# 2_waffling60-ALPS_matrix.net
KiCad netlist of a schematic drawn in Altium Designer
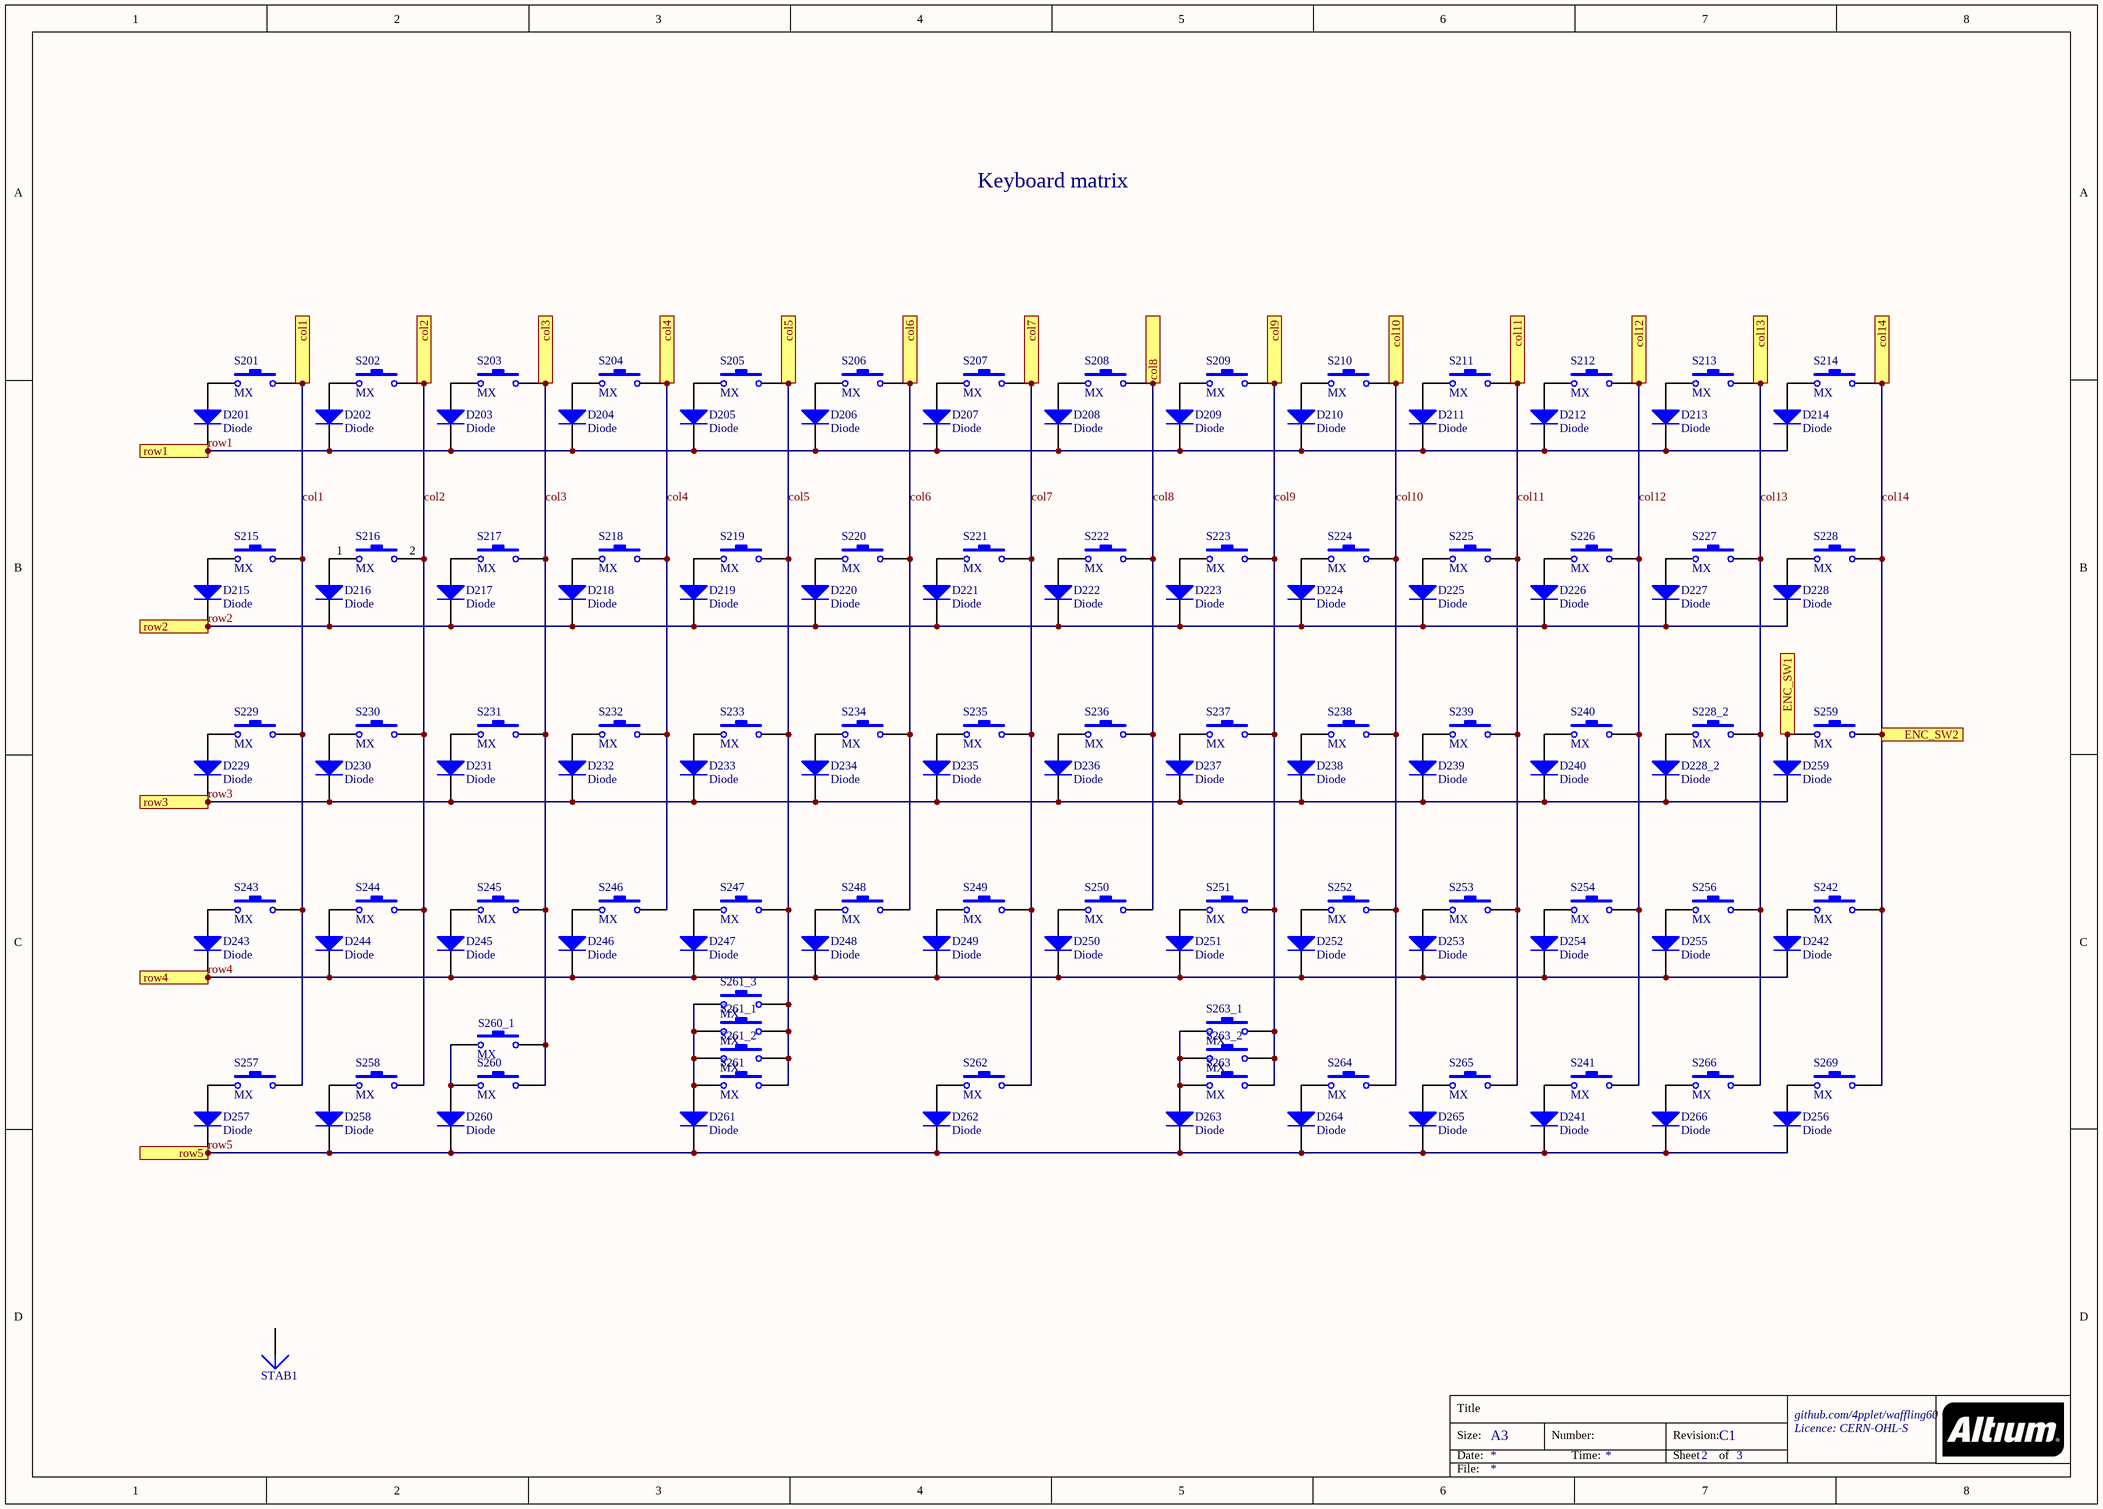
[diagram p0: 2_waffling60-ALPS_matrix.SchDoc]

(export (version "E")
  (design (tool "Eeschema 10.0.6"))
  (components
    (comp (ref "D201")
      (value "Diode")
      (footprint "SOD-123")
      (description "Default Diode")
      (fields (field (name "LCSC PART #") "C81598") (field (name "MRF.PART") "1N4148W"))
      (libsource (lib "Miscellaneous Devices") (part "Diode"))
    )
    (comp (ref "D202")
      (value "Diode")
      (footprint "SOD-123")
      (description "Default Diode")
      (fields (field (name "LCSC PART #") "C81598") (field (name "MRF.PART") "1N4148W"))
      (libsource (lib "Miscellaneous Devices") (part "Diode"))
    )
    (comp (ref "D203")
      (value "Diode")
      (footprint "SOD-123")
      (description "Default Diode")
      (fields (field (name "LCSC PART #") "C81598") (field (name "MRF.PART") "1N4148W"))
      (libsource (lib "Miscellaneous Devices") (part "Diode"))
    )
    (comp (ref "D204")
      (value "Diode")
      (footprint "SOD-123")
      (description "Default Diode")
      (fields (field (name "LCSC PART #") "C81598") (field (name "MRF.PART") "1N4148W"))
      (libsource (lib "Miscellaneous Devices") (part "Diode"))
    )
    (comp (ref "D205")
      (value "Diode")
      (footprint "SOD-123")
      (description "Default Diode")
      (fields (field (name "LCSC PART #") "C81598") (field (name "MRF.PART") "1N4148W"))
      (libsource (lib "Miscellaneous Devices") (part "Diode"))
    )
    (comp (ref "D206")
      (value "Diode")
      (footprint "SOD-123")
      (description "Default Diode")
      (fields (field (name "LCSC PART #") "C81598") (field (name "MRF.PART") "1N4148W"))
      (libsource (lib "Miscellaneous Devices") (part "Diode"))
    )
    (comp (ref "D207")
      (value "Diode")
      (footprint "SOD-123")
      (description "Default Diode")
      (fields (field (name "LCSC PART #") "C81598") (field (name "MRF.PART") "1N4148W"))
      (libsource (lib "Miscellaneous Devices") (part "Diode"))
    )
    (comp (ref "D208")
      (value "Diode")
      (footprint "SOD-123")
      (description "Default Diode")
      (fields (field (name "LCSC PART #") "C81598") (field (name "MRF.PART") "1N4148W"))
      (libsource (lib "Miscellaneous Devices") (part "Diode"))
    )
    (comp (ref "D209")
      (value "Diode")
      (footprint "SOD-123")
      (description "Default Diode")
      (fields (field (name "LCSC PART #") "C81598") (field (name "MRF.PART") "1N4148W"))
      (libsource (lib "Miscellaneous Devices") (part "Diode"))
    )
    (comp (ref "D210")
      (value "Diode")
      (footprint "SOD-123")
      (description "Default Diode")
      (fields (field (name "LCSC PART #") "C81598") (field (name "MRF.PART") "1N4148W"))
      (libsource (lib "Miscellaneous Devices") (part "Diode"))
    )
    (comp (ref "D211")
      (value "Diode")
      (footprint "SOD-123")
      (description "Default Diode")
      (fields (field (name "LCSC PART #") "C81598") (field (name "MRF.PART") "1N4148W"))
      (libsource (lib "Miscellaneous Devices") (part "Diode"))
    )
    (comp (ref "D212")
      (value "Diode")
      (footprint "SOD-123")
      (description "Default Diode")
      (fields (field (name "LCSC PART #") "C81598") (field (name "MRF.PART") "1N4148W"))
      (libsource (lib "Miscellaneous Devices") (part "Diode"))
    )
    (comp (ref "D213")
      (value "Diode")
      (footprint "SOD-123")
      (description "Default Diode")
      (fields (field (name "LCSC PART #") "C81598") (field (name "MRF.PART") "1N4148W"))
      (libsource (lib "Miscellaneous Devices") (part "Diode"))
    )
    (comp (ref "D214")
      (value "Diode")
      (footprint "SOD-123")
      (description "Default Diode")
      (fields (field (name "LCSC PART #") "C81598") (field (name "MRF.PART") "1N4148W"))
      (libsource (lib "Miscellaneous Devices") (part "Diode"))
    )
    (comp (ref "D215")
      (value "Diode")
      (footprint "SOD-123")
      (description "Default Diode")
      (fields (field (name "LCSC PART #") "C81598") (field (name "MRF.PART") "1N4148W"))
      (libsource (lib "Miscellaneous Devices") (part "Diode"))
    )
    (comp (ref "D216")
      (value "Diode")
      (footprint "SOD-123")
      (description "Default Diode")
      (fields (field (name "LCSC PART #") "C81598") (field (name "MRF.PART") "1N4148W"))
      (libsource (lib "Miscellaneous Devices") (part "Diode"))
    )
    (comp (ref "D217")
      (value "Diode")
      (footprint "SOD-123")
      (description "Default Diode")
      (fields (field (name "LCSC PART #") "C81598") (field (name "MRF.PART") "1N4148W"))
      (libsource (lib "Miscellaneous Devices") (part "Diode"))
    )
    (comp (ref "D218")
      (value "Diode")
      (footprint "SOD-123")
      (description "Default Diode")
      (fields (field (name "LCSC PART #") "C81598") (field (name "MRF.PART") "1N4148W"))
      (libsource (lib "Miscellaneous Devices") (part "Diode"))
    )
    (comp (ref "D219")
      (value "Diode")
      (footprint "SOD-123")
      (description "Default Diode")
      (fields (field (name "LCSC PART #") "C81598") (field (name "MRF.PART") "1N4148W"))
      (libsource (lib "Miscellaneous Devices") (part "Diode"))
    )
    (comp (ref "D220")
      (value "Diode")
      (footprint "SOD-123")
      (description "Default Diode")
      (fields (field (name "LCSC PART #") "C81598") (field (name "MRF.PART") "1N4148W"))
      (libsource (lib "Miscellaneous Devices") (part "Diode"))
    )
    (comp (ref "D221")
      (value "Diode")
      (footprint "SOD-123")
      (description "Default Diode")
      (fields (field (name "LCSC PART #") "C81598") (field (name "MRF.PART") "1N4148W"))
      (libsource (lib "Miscellaneous Devices") (part "Diode"))
    )
    (comp (ref "D222")
      (value "Diode")
      (footprint "SOD-123")
      (description "Default Diode")
      (fields (field (name "LCSC PART #") "C81598") (field (name "MRF.PART") "1N4148W"))
      (libsource (lib "Miscellaneous Devices") (part "Diode"))
    )
    (comp (ref "D223")
      (value "Diode")
      (footprint "SOD-123")
      (description "Default Diode")
      (fields (field (name "LCSC PART #") "C81598") (field (name "MRF.PART") "1N4148W"))
      (libsource (lib "Miscellaneous Devices") (part "Diode"))
    )
    (comp (ref "D224")
      (value "Diode")
      (footprint "SOD-123")
      (description "Default Diode")
      (fields (field (name "LCSC PART #") "C81598") (field (name "MRF.PART") "1N4148W"))
      (libsource (lib "Miscellaneous Devices") (part "Diode"))
    )
    (comp (ref "D225")
      (value "Diode")
      (footprint "SOD-123")
      (description "Default Diode")
      (fields (field (name "LCSC PART #") "C81598") (field (name "MRF.PART") "1N4148W"))
      (libsource (lib "Miscellaneous Devices") (part "Diode"))
    )
    (comp (ref "D226")
      (value "Diode")
      (footprint "SOD-123")
      (description "Default Diode")
      (fields (field (name "LCSC PART #") "C81598") (field (name "MRF.PART") "1N4148W"))
      (libsource (lib "Miscellaneous Devices") (part "Diode"))
    )
    (comp (ref "D227")
      (value "Diode")
      (footprint "SOD-123")
      (description "Default Diode")
      (fields (field (name "LCSC PART #") "C81598") (field (name "MRF.PART") "1N4148W"))
      (libsource (lib "Miscellaneous Devices") (part "Diode"))
    )
    (comp (ref "D228")
      (value "Diode")
      (footprint "SOD-123")
      (description "Default Diode")
      (fields (field (name "LCSC PART #") "C81598") (field (name "MRF.PART") "1N4148W"))
      (libsource (lib "Miscellaneous Devices") (part "Diode"))
    )
    (comp (ref "D228_2")
      (value "Diode")
      (footprint "SOD-123")
      (description "Default Diode")
      (fields (field (name "LCSC PART #") "C81598") (field (name "MRF.PART") "1N4148W"))
      (libsource (lib "Miscellaneous Devices") (part "Diode"))
    )
    (comp (ref "D229")
      (value "Diode")
      (footprint "SOD-123")
      (description "Default Diode")
      (fields (field (name "LCSC PART #") "C81598") (field (name "MRF.PART") "1N4148W"))
      (libsource (lib "Miscellaneous Devices") (part "Diode"))
    )
    (comp (ref "D230")
      (value "Diode")
      (footprint "SOD-123")
      (description "Default Diode")
      (fields (field (name "LCSC PART #") "C81598") (field (name "MRF.PART") "1N4148W"))
      (libsource (lib "Miscellaneous Devices") (part "Diode"))
    )
    (comp (ref "D231")
      (value "Diode")
      (footprint "SOD-123")
      (description "Default Diode")
      (fields (field (name "LCSC PART #") "C81598") (field (name "MRF.PART") "1N4148W"))
      (libsource (lib "Miscellaneous Devices") (part "Diode"))
    )
    (comp (ref "D232")
      (value "Diode")
      (footprint "SOD-123")
      (description "Default Diode")
      (fields (field (name "LCSC PART #") "C81598") (field (name "MRF.PART") "1N4148W"))
      (libsource (lib "Miscellaneous Devices") (part "Diode"))
    )
    (comp (ref "D233")
      (value "Diode")
      (footprint "SOD-123")
      (description "Default Diode")
      (fields (field (name "LCSC PART #") "C81598") (field (name "MRF.PART") "1N4148W"))
      (libsource (lib "Miscellaneous Devices") (part "Diode"))
    )
    (comp (ref "D234")
      (value "Diode")
      (footprint "SOD-123")
      (description "Default Diode")
      (fields (field (name "LCSC PART #") "C81598") (field (name "MRF.PART") "1N4148W"))
      (libsource (lib "Miscellaneous Devices") (part "Diode"))
    )
    (comp (ref "D235")
      (value "Diode")
      (footprint "SOD-123")
      (description "Default Diode")
      (fields (field (name "LCSC PART #") "C81598") (field (name "MRF.PART") "1N4148W"))
      (libsource (lib "Miscellaneous Devices") (part "Diode"))
    )
    (comp (ref "D236")
      (value "Diode")
      (footprint "SOD-123")
      (description "Default Diode")
      (fields (field (name "LCSC PART #") "C81598") (field (name "MRF.PART") "1N4148W"))
      (libsource (lib "Miscellaneous Devices") (part "Diode"))
    )
    (comp (ref "D237")
      (value "Diode")
      (footprint "SOD-123")
      (description "Default Diode")
      (fields (field (name "LCSC PART #") "C81598") (field (name "MRF.PART") "1N4148W"))
      (libsource (lib "Miscellaneous Devices") (part "Diode"))
    )
    (comp (ref "D238")
      (value "Diode")
      (footprint "SOD-123")
      (description "Default Diode")
      (fields (field (name "LCSC PART #") "C81598") (field (name "MRF.PART") "1N4148W"))
      (libsource (lib "Miscellaneous Devices") (part "Diode"))
    )
    (comp (ref "D239")
      (value "Diode")
      (footprint "SOD-123")
      (description "Default Diode")
      (fields (field (name "LCSC PART #") "C81598") (field (name "MRF.PART") "1N4148W"))
      (libsource (lib "Miscellaneous Devices") (part "Diode"))
    )
    (comp (ref "D240")
      (value "Diode")
      (footprint "SOD-123")
      (description "Default Diode")
      (fields (field (name "LCSC PART #") "C81598") (field (name "MRF.PART") "1N4148W"))
      (libsource (lib "Miscellaneous Devices") (part "Diode"))
    )
    (comp (ref "D241")
      (value "Diode")
      (footprint "SOD-123")
      (description "Default Diode")
      (fields (field (name "LCSC PART #") "C81598") (field (name "MRF.PART") "1N4148W"))
      (libsource (lib "Miscellaneous Devices") (part "Diode"))
    )
    (comp (ref "D242")
      (value "Diode")
      (footprint "SOD-123")
      (description "Default Diode")
      (fields (field (name "LCSC PART #") "C81598") (field (name "MRF.PART") "1N4148W"))
      (libsource (lib "Miscellaneous Devices") (part "Diode"))
    )
    (comp (ref "D243")
      (value "Diode")
      (footprint "SOD-123")
      (description "Default Diode")
      (fields (field (name "LCSC PART #") "C81598") (field (name "MRF.PART") "1N4148W"))
      (libsource (lib "Miscellaneous Devices") (part "Diode"))
    )
    (comp (ref "D244")
      (value "Diode")
      (footprint "SOD-123")
      (description "Default Diode")
      (fields (field (name "LCSC PART #") "C81598") (field (name "MRF.PART") "1N4148W"))
      (libsource (lib "Miscellaneous Devices") (part "Diode"))
    )
    (comp (ref "D245")
      (value "Diode")
      (footprint "SOD-123")
      (description "Default Diode")
      (fields (field (name "LCSC PART #") "C81598") (field (name "MRF.PART") "1N4148W"))
      (libsource (lib "Miscellaneous Devices") (part "Diode"))
    )
    (comp (ref "D246")
      (value "Diode")
      (footprint "SOD-123")
      (description "Default Diode")
      (fields (field (name "LCSC PART #") "C81598") (field (name "MRF.PART") "1N4148W"))
      (libsource (lib "Miscellaneous Devices") (part "Diode"))
    )
    (comp (ref "D247")
      (value "Diode")
      (footprint "SOD-123")
      (description "Default Diode")
      (fields (field (name "LCSC PART #") "C81598") (field (name "MRF.PART") "1N4148W"))
      (libsource (lib "Miscellaneous Devices") (part "Diode"))
    )
    (comp (ref "D248")
      (value "Diode")
      (footprint "SOD-123")
      (description "Default Diode")
      (fields (field (name "LCSC PART #") "C81598") (field (name "MRF.PART") "1N4148W"))
      (libsource (lib "Miscellaneous Devices") (part "Diode"))
    )
    (comp (ref "D249")
      (value "Diode")
      (footprint "SOD-123")
      (description "Default Diode")
      (fields (field (name "LCSC PART #") "C81598") (field (name "MRF.PART") "1N4148W"))
      (libsource (lib "Miscellaneous Devices") (part "Diode"))
    )
    (comp (ref "D250")
      (value "Diode")
      (footprint "SOD-123")
      (description "Default Diode")
      (fields (field (name "LCSC PART #") "C81598") (field (name "MRF.PART") "1N4148W"))
      (libsource (lib "Miscellaneous Devices") (part "Diode"))
    )
    (comp (ref "D251")
      (value "Diode")
      (footprint "SOD-123")
      (description "Default Diode")
      (fields (field (name "LCSC PART #") "C81598") (field (name "MRF.PART") "1N4148W"))
      (libsource (lib "Miscellaneous Devices") (part "Diode"))
    )
    (comp (ref "D252")
      (value "Diode")
      (footprint "SOD-123")
      (description "Default Diode")
      (fields (field (name "LCSC PART #") "C81598") (field (name "MRF.PART") "1N4148W"))
      (libsource (lib "Miscellaneous Devices") (part "Diode"))
    )
    (comp (ref "D253")
      (value "Diode")
      (footprint "SOD-123")
      (description "Default Diode")
      (fields (field (name "LCSC PART #") "C81598") (field (name "MRF.PART") "1N4148W"))
      (libsource (lib "Miscellaneous Devices") (part "Diode"))
    )
    (comp (ref "D254")
      (value "Diode")
      (footprint "SOD-123")
      (description "Default Diode")
      (fields (field (name "LCSC PART #") "C81598") (field (name "MRF.PART") "1N4148W"))
      (libsource (lib "Miscellaneous Devices") (part "Diode"))
    )
    (comp (ref "D255")
      (value "Diode")
      (footprint "SOD-123")
      (description "Default Diode")
      (fields (field (name "LCSC PART #") "C81598") (field (name "MRF.PART") "1N4148W"))
      (libsource (lib "Miscellaneous Devices") (part "Diode"))
    )
    (comp (ref "D256")
      (value "Diode")
      (footprint "SOD-123")
      (description "Default Diode")
      (fields (field (name "LCSC PART #") "C81598") (field (name "MRF.PART") "1N4148W"))
      (libsource (lib "Miscellaneous Devices") (part "Diode"))
    )
    (comp (ref "D257")
      (value "Diode")
      (footprint "SOD-123")
      (description "Default Diode")
      (fields (field (name "LCSC PART #") "C81598") (field (name "MRF.PART") "1N4148W"))
      (libsource (lib "Miscellaneous Devices") (part "Diode"))
    )
    (comp (ref "D258")
      (value "Diode")
      (footprint "SOD-123")
      (description "Default Diode")
      (fields (field (name "LCSC PART #") "C81598") (field (name "MRF.PART") "1N4148W"))
      (libsource (lib "Miscellaneous Devices") (part "Diode"))
    )
    (comp (ref "D259")
      (value "Diode")
      (footprint "SOD-123")
      (description "Default Diode")
      (fields (field (name "LCSC PART #") "C81598") (field (name "MRF.PART") "1N4148W"))
      (libsource (lib "Miscellaneous Devices") (part "Diode"))
    )
    (comp (ref "D260")
      (value "Diode")
      (footprint "SOD-123")
      (description "Default Diode")
      (fields (field (name "LCSC PART #") "C81598") (field (name "MRF.PART") "1N4148W"))
      (libsource (lib "Miscellaneous Devices") (part "Diode"))
    )
    (comp (ref "D261")
      (value "Diode")
      (footprint "SOD-123")
      (description "Default Diode")
      (fields (field (name "LCSC PART #") "C81598") (field (name "MRF.PART") "1N4148W"))
      (libsource (lib "Miscellaneous Devices") (part "Diode"))
    )
    (comp (ref "D262")
      (value "Diode")
      (footprint "SOD-123")
      (description "Default Diode")
      (fields (field (name "LCSC PART #") "C81598") (field (name "MRF.PART") "1N4148W"))
      (libsource (lib "Miscellaneous Devices") (part "Diode"))
    )
    (comp (ref "D263")
      (value "Diode")
      (footprint "SOD-123")
      (description "Default Diode")
      (fields (field (name "LCSC PART #") "C81598") (field (name "MRF.PART") "1N4148W"))
      (libsource (lib "Miscellaneous Devices") (part "Diode"))
    )
    (comp (ref "D264")
      (value "Diode")
      (footprint "SOD-123")
      (description "Default Diode")
      (fields (field (name "LCSC PART #") "C81598") (field (name "MRF.PART") "1N4148W"))
      (libsource (lib "Miscellaneous Devices") (part "Diode"))
    )
    (comp (ref "D265")
      (value "Diode")
      (footprint "SOD-123")
      (description "Default Diode")
      (fields (field (name "LCSC PART #") "C81598") (field (name "MRF.PART") "1N4148W"))
      (libsource (lib "Miscellaneous Devices") (part "Diode"))
    )
    (comp (ref "D266")
      (value "Diode")
      (footprint "SOD-123")
      (description "Default Diode")
      (fields (field (name "LCSC PART #") "C81598") (field (name "MRF.PART") "1N4148W"))
      (libsource (lib "Miscellaneous Devices") (part "Diode"))
    )
    (comp (ref "S201")
      (value "MX")
      (footprint "Alps-switch - switched pol")
      (description "Switch")
      (libsource (lib "Miscellaneous Devices") (part "SW-PB"))
    )
    (comp (ref "S202")
      (value "MX")
      (footprint "Alps-switch - switched pol")
      (description "Switch")
      (libsource (lib "Miscellaneous Devices") (part "SW-PB"))
    )
    (comp (ref "S203")
      (value "MX")
      (footprint "Alps-switch - switched pol")
      (description "Switch")
      (libsource (lib "Miscellaneous Devices") (part "SW-PB"))
    )
    (comp (ref "S204")
      (value "MX")
      (footprint "Alps-switch - switched pol")
      (description "Switch")
      (libsource (lib "Miscellaneous Devices") (part "SW-PB"))
    )
    (comp (ref "S205")
      (value "MX")
      (footprint "Alps-switch - switched pol")
      (description "Switch")
      (libsource (lib "Miscellaneous Devices") (part "SW-PB"))
    )
    (comp (ref "S206")
      (value "MX")
      (footprint "Alps-switch - switched pol")
      (description "Switch")
      (libsource (lib "Miscellaneous Devices") (part "SW-PB"))
    )
    (comp (ref "S207")
      (value "MX")
      (footprint "Alps-switch - switched pol")
      (description "Switch")
      (libsource (lib "Miscellaneous Devices") (part "SW-PB"))
    )
    (comp (ref "S208")
      (value "MX")
      (footprint "Alps-switch - switched pol")
      (description "Switch")
      (libsource (lib "Miscellaneous Devices") (part "SW-PB"))
    )
    (comp (ref "S209")
      (value "MX")
      (footprint "Alps-switch - switched pol")
      (description "Switch")
      (libsource (lib "Miscellaneous Devices") (part "SW-PB"))
    )
    (comp (ref "S210")
      (value "MX")
      (footprint "Alps-switch - switched pol")
      (description "Switch")
      (libsource (lib "Miscellaneous Devices") (part "SW-PB"))
    )
    (comp (ref "S211")
      (value "MX")
      (footprint "Alps-switch - switched pol")
      (description "Switch")
      (libsource (lib "Miscellaneous Devices") (part "SW-PB"))
    )
    (comp (ref "S212")
      (value "MX")
      (footprint "Alps-switch - switched pol")
      (description "Switch")
      (libsource (lib "Miscellaneous Devices") (part "SW-PB"))
    )
    (comp (ref "S213")
      (value "MX")
      (footprint "Alps-switch - switched pol")
      (description "Switch")
      (libsource (lib "Miscellaneous Devices") (part "SW-PB"))
    )
    (comp (ref "S214")
      (value "MX")
      (footprint "Alps-switch")
      (description "Switch")
      (libsource (lib "Miscellaneous Devices") (part "SW-PB"))
    )
    (comp (ref "S215")
      (value "MX")
      (footprint "Alps-switch - switched pol")
      (description "TAB")
      (libsource (lib "Miscellaneous Devices") (part "SW-PB"))
    )
    (comp (ref "S216")
      (value "MX")
      (footprint "Alps-switch")
      (description "Switch")
      (libsource (lib "") (part "SW-PB_1"))
    )
    (comp (ref "S217")
      (value "MX")
      (footprint "Alps-switch - switched pol")
      (description "Switch")
      (libsource (lib "Miscellaneous Devices") (part "SW-PB"))
    )
    (comp (ref "S218")
      (value "MX")
      (footprint "Alps-switch - switched pol")
      (description "Switch")
      (libsource (lib "Miscellaneous Devices") (part "SW-PB"))
    )
    (comp (ref "S219")
      (value "MX")
      (footprint "Alps-switch - switched pol")
      (description "Switch")
      (libsource (lib "Miscellaneous Devices") (part "SW-PB"))
    )
    (comp (ref "S220")
      (value "MX")
      (footprint "Alps-switch - switched pol")
      (description "Switch")
      (libsource (lib "Miscellaneous Devices") (part "SW-PB"))
    )
    (comp (ref "S221")
      (value "MX")
      (footprint "Alps-switch - switched pol")
      (description "Switch")
      (libsource (lib "Miscellaneous Devices") (part "SW-PB"))
    )
    (comp (ref "S222")
      (value "MX")
      (footprint "Alps-switch - switched pol")
      (description "Switch")
      (libsource (lib "Miscellaneous Devices") (part "SW-PB"))
    )
    (comp (ref "S223")
      (value "MX")
      (footprint "Alps-switch - switched pol")
      (description "Switch")
      (libsource (lib "Miscellaneous Devices") (part "SW-PB"))
    )
    (comp (ref "S224")
      (value "MX")
      (footprint "Alps-switch - switched pol")
      (description "Switch")
      (libsource (lib "Miscellaneous Devices") (part "SW-PB"))
    )
    (comp (ref "S225")
      (value "MX")
      (footprint "Alps-switch - switched pol")
      (description "Switch")
      (libsource (lib "Miscellaneous Devices") (part "SW-PB"))
    )
    (comp (ref "S226")
      (value "MX")
      (footprint "Alps-switch")
      (description "Switch")
      (libsource (lib "Miscellaneous Devices") (part "SW-PB"))
    )
    (comp (ref "S227")
      (value "MX")
      (footprint "Alps-switch")
      (description "Switch")
      (libsource (lib "Miscellaneous Devices") (part "SW-PB"))
    )
    (comp (ref "S228")
      (value "MX")
      (footprint "Alps-switch")
      (description "Switch")
      (libsource (lib "Miscellaneous Devices") (part "SW-PB"))
    )
    (comp (ref "S228_2")
      (value "MX")
      (footprint "Alps-switch - switched pol")
      (description "Switch")
      (libsource (lib "Miscellaneous Devices") (part "SW-PB"))
    )
    (comp (ref "S229")
      (value "MX")
      (footprint "ALPS-switch - CAPS")
      (description "Switch")
      (libsource (lib "Miscellaneous Devices") (part "SW-PB"))
    )
    (comp (ref "S230")
      (value "MX")
      (footprint "Alps-switch")
      (description "Switch")
      (libsource (lib "Miscellaneous Devices") (part "SW-PB"))
    )
    (comp (ref "S231")
      (value "MX")
      (footprint "Alps-switch - switched pol")
      (description "Switch")
      (libsource (lib "Miscellaneous Devices") (part "SW-PB"))
    )
    (comp (ref "S232")
      (value "MX")
      (footprint "Alps-switch - switched pol")
      (description "Switch")
      (libsource (lib "Miscellaneous Devices") (part "SW-PB"))
    )
    (comp (ref "S233")
      (value "MX")
      (footprint "Alps-switch - switched pol")
      (description "Switch")
      (libsource (lib "Miscellaneous Devices") (part "SW-PB"))
    )
    (comp (ref "S234")
      (value "MX")
      (footprint "Alps-switch")
      (description "Switch")
      (libsource (lib "Miscellaneous Devices") (part "SW-PB"))
    )
    (comp (ref "S235")
      (value "MX")
      (footprint "Alps-switch - switched pol")
      (description "Switch")
      (libsource (lib "Miscellaneous Devices") (part "SW-PB"))
    )
    (comp (ref "S236")
      (value "MX")
      (footprint "Alps-switch - switched pol")
      (description "Switch")
      (libsource (lib "Miscellaneous Devices") (part "SW-PB"))
    )
    (comp (ref "S237")
      (value "MX")
      (footprint "Alps-switch - switched pol")
      (description "Switch")
      (libsource (lib "Miscellaneous Devices") (part "SW-PB"))
    )
    (comp (ref "S238")
      (value "MX")
      (footprint "Alps-switch - switched pol")
      (description "Switch")
      (libsource (lib "Miscellaneous Devices") (part "SW-PB"))
    )
    (comp (ref "S239")
      (value "MX")
      (footprint "Alps-switch - switched pol")
      (description "Switch")
      (libsource (lib "Miscellaneous Devices") (part "SW-PB"))
    )
    (comp (ref "S240")
      (value "MX")
      (footprint "Alps-switch - switched pol")
      (description "Switch")
      (libsource (lib "Miscellaneous Devices") (part "SW-PB"))
    )
    (comp (ref "S241")
      (value "MX")
      (footprint "ALPS-switch - R_WIN V3")
      (description "Switch")
      (libsource (lib "Miscellaneous Devices") (part "SW-PB"))
    )
    (comp (ref "S242")
      (value "MX")
      (description "Switch")
      (libsource (lib "Miscellaneous Devices") (part "SW-PB"))
    )
    (comp (ref "S243")
      (value "MX")
      (footprint "ALPS-switch - Left shift v2")
      (description "Switch")
      (libsource (lib "Miscellaneous Devices") (part "SW-PB"))
    )
    (comp (ref "S244")
      (value "MX")
      (footprint "Alps-switch")
      (description "Switch")
      (libsource (lib "Miscellaneous Devices") (part "SW-PB"))
    )
    (comp (ref "S245")
      (value "MX")
      (footprint "Alps-switch - switched pol")
      (description "Switch")
      (libsource (lib "Miscellaneous Devices") (part "SW-PB"))
    )
    (comp (ref "S246")
      (value "MX")
      (footprint "Alps-switch - switched pol")
      (description "Switch")
      (libsource (lib "Miscellaneous Devices") (part "SW-PB"))
    )
    (comp (ref "S247")
      (value "MX")
      (footprint "Alps-switch - switched pol")
      (description "Switch")
      (libsource (lib "Miscellaneous Devices") (part "SW-PB"))
    )
    (comp (ref "S248")
      (value "MX")
      (footprint "Alps-switch - switched pol")
      (description "Switch")
      (libsource (lib "Miscellaneous Devices") (part "SW-PB"))
    )
    (comp (ref "S249")
      (value "MX")
      (footprint "Alps-switch - switched pol")
      (description "Switch")
      (libsource (lib "Miscellaneous Devices") (part "SW-PB"))
    )
    (comp (ref "S250")
      (value "MX")
      (footprint "Alps-switch - switched pol")
      (description "Switch")
      (libsource (lib "Miscellaneous Devices") (part "SW-PB"))
    )
    (comp (ref "S251")
      (value "MX")
      (footprint "Alps-switch - switched pol")
      (description "Switch")
      (libsource (lib "Miscellaneous Devices") (part "SW-PB"))
    )
    (comp (ref "S252")
      (value "MX")
      (footprint "Alps-switch - switched pol")
      (description "Switch")
      (libsource (lib "Miscellaneous Devices") (part "SW-PB"))
    )
    (comp (ref "S253")
      (value "MX")
      (footprint "Alps-switch - switched pol")
      (description "Switch")
      (libsource (lib "Miscellaneous Devices") (part "SW-PB"))
    )
    (comp (ref "S254")
      (value "MX")
      (footprint "Alps-switch - switched pol")
      (description "Switch")
      (libsource (lib "Miscellaneous Devices") (part "SW-PB"))
    )
    (comp (ref "S256")
      (value "MX")
      (footprint "ALPS-switch - right shift - stabs")
      (description "Switch")
      (libsource (lib "Miscellaneous Devices") (part "SW-PB"))
    )
    (comp (ref "S257")
      (value "MX")
      (footprint "ALPS-switch - 1.5u MOD-L")
      (description "Switch")
      (libsource (lib "Miscellaneous Devices") (part "SW-PB"))
    )
    (comp (ref "S258")
      (value "MX")
      (footprint "ALPS-switch - L_WIN - V3")
      (description "Switch")
      (libsource (lib "Miscellaneous Devices") (part "SW-PB"))
    )
    (comp (ref "S259")
      (value "MX")
      (footprint "ALPS-switch - backspace")
      (description "Switch")
      (libsource (lib "Miscellaneous Devices") (part "SW-PB"))
    )
    (comp (ref "S260")
      (value "MX")
      (footprint "ALPS-SWITCH - L_ALT - V3")
      (description "Switch")
      (libsource (lib "Miscellaneous Devices") (part "SW-PB"))
    )
    (comp (ref "S260_1")
      (value "MX")
      (footprint "Alps-switch")
      (description "Switch")
      (libsource (lib "Miscellaneous Devices") (part "SW-PB"))
    )
    (comp (ref "S261")
      (value "MX")
      (footprint "ALPS-switch - L split space_V3")
      (description "Switch")
      (libsource (lib "Miscellaneous Devices") (part "SW-PB"))
    )
    (comp (ref "S261_1")
      (value "MX")
      (footprint "Alps-switch - switched pol")
      (description "Switch")
      (libsource (lib "Miscellaneous Devices") (part "SW-PB"))
    )
    (comp (ref "S261_2")
      (value "MX")
      (footprint "ALPS-switch - 3U - rotated stab")
      (description "Switch")
      (libsource (lib "Miscellaneous Devices") (part "SW-PB"))
    )
    (comp (ref "S261_3")
      (value "MX")
      (footprint "Alps-switch - switched pol")
      (description "Switch")
      (libsource (lib "Miscellaneous Devices") (part "SW-PB"))
    )
    (comp (ref "S262")
      (value "MX")
      (footprint "ALPS-switch - Space_V3")
      (description "Switch")
      (libsource (lib "Miscellaneous Devices") (part "SW-PB"))
    )
    (comp (ref "S263")
      (value "MX")
      (footprint "ALPS-switch - R split space_V3")
      (description "Switch")
      (libsource (lib "Miscellaneous Devices") (part "SW-PB"))
    )
    (comp (ref "S263_1")
      (value "MX")
      (footprint "Alps-switch")
      (description "Switch")
      (libsource (lib "Miscellaneous Devices") (part "SW-PB"))
    )
    (comp (ref "S263_2")
      (value "MX")
      (footprint "ALPS-switch - 3U - rotated stab")
      (description "Switch")
      (libsource (lib "Miscellaneous Devices") (part "SW-PB"))
    )
    (comp (ref "S264")
      (value "MX")
      (footprint "Alps-switch - switched pol")
      (description "Switch")
      (libsource (lib "Miscellaneous Devices") (part "SW-PB"))
    )
    (comp (ref "S265")
      (value "MX")
      (footprint "ALPS-SWITCH - R_ALT - V3")
      (description "Switch")
      (libsource (lib "Miscellaneous Devices") (part "SW-PB"))
    )
    (comp (ref "S266")
      (value "MX")
      (footprint "ALPS-switch - 1.5u MOD-R")
      (description "Switch")
      (libsource (lib "Miscellaneous Devices") (part "SW-PB"))
    )
    (comp (ref "S269")
      (value "MX")
      (footprint "Alps-switch")
      (description "Switch")
      (libsource (lib "Miscellaneous Devices") (part "SW-PB"))
    )
    (comp (ref "STAB1")
      (value "Plug")
      (footprint "Stab 10U")
      (libsource (lib "Miscellaneous Connectors") (part "Plug"))
    )
  )
  (nets
    (net (code "1") (name "/ENC_SW1") (class "Default")
      (node (ref "D259") (pin "1") (pinfunction "A_1") (pintype "passive"))
      (node (ref "S259") (pin "1") (pinfunction "1_1") (pintype "passive"))
    )
    (net (code "2") (name "/col1") (class "Default")
      (node (ref "S201") (pin "2") (pinfunction "2_2") (pintype "passive"))
      (node (ref "S215") (pin "2") (pinfunction "2_2") (pintype "passive"))
      (node (ref "S229") (pin "2") (pinfunction "2_2") (pintype "passive"))
      (node (ref "S243") (pin "2") (pinfunction "2_2") (pintype "passive"))
      (node (ref "S257") (pin "1") (pinfunction "1_1") (pintype "passive"))
    )
    (net (code "3") (name "/col2") (class "Default")
      (node (ref "S202") (pin "2") (pinfunction "2_2") (pintype "passive"))
      (node (ref "S216") (pin "2") (pinfunction "2_2") (pintype "passive"))
      (node (ref "S230") (pin "2") (pinfunction "2_2") (pintype "passive"))
      (node (ref "S244") (pin "1") (pinfunction "1_1") (pintype "passive"))
      (node (ref "S258") (pin "2") (pinfunction "2_2") (pintype "passive"))
    )
    (net (code "4") (name "/col3") (class "Default")
      (node (ref "S203") (pin "2") (pinfunction "2_2") (pintype "passive"))
      (node (ref "S217") (pin "2") (pinfunction "2_2") (pintype "passive"))
      (node (ref "S231") (pin "2") (pinfunction "2_2") (pintype "passive"))
      (node (ref "S245") (pin "2") (pinfunction "2_2") (pintype "passive"))
      (node (ref "S260") (pin "2") (pinfunction "2_2") (pintype "passive"))
      (node (ref "S260_1") (pin "2") (pinfunction "2_2") (pintype "passive"))
    )
    (net (code "5") (name "/col4") (class "Default")
      (node (ref "S204") (pin "2") (pinfunction "2_2") (pintype "passive"))
      (node (ref "S218") (pin "2") (pinfunction "2_2") (pintype "passive"))
      (node (ref "S232") (pin "2") (pinfunction "2_2") (pintype "passive"))
      (node (ref "S246") (pin "2") (pinfunction "2_2") (pintype "passive"))
    )
    (net (code "6") (name "/col5") (class "Default")
      (node (ref "S205") (pin "2") (pinfunction "2_2") (pintype "passive"))
      (node (ref "S219") (pin "2") (pinfunction "2_2") (pintype "passive"))
      (node (ref "S233") (pin "2") (pinfunction "2_2") (pintype "passive"))
      (node (ref "S247") (pin "2") (pinfunction "2_2") (pintype "passive"))
      (node (ref "S261") (pin "2") (pinfunction "2_2") (pintype "passive"))
      (node (ref "S261_1") (pin "2") (pinfunction "2_2") (pintype "passive"))
      (node (ref "S261_2") (pin "1") (pinfunction "1_1") (pintype "passive"))
      (node (ref "S261_3") (pin "2") (pinfunction "2_2") (pintype "passive"))
    )
    (net (code "7") (name "/col6") (class "Default")
      (node (ref "S206") (pin "2") (pinfunction "2_2") (pintype "passive"))
      (node (ref "S220") (pin "2") (pinfunction "2_2") (pintype "passive"))
      (node (ref "S234") (pin "2") (pinfunction "2_2") (pintype "passive"))
      (node (ref "S248") (pin "2") (pinfunction "2_2") (pintype "passive"))
    )
    (net (code "8") (name "/col7") (class "Default")
      (node (ref "S207") (pin "2") (pinfunction "2_2") (pintype "passive"))
      (node (ref "S221") (pin "2") (pinfunction "2_2") (pintype "passive"))
      (node (ref "S235") (pin "2") (pinfunction "2_2") (pintype "passive"))
      (node (ref "S249") (pin "2") (pinfunction "2_2") (pintype "passive"))
      (node (ref "S262") (pin "1") (pinfunction "1_1") (pintype "passive"))
    )
    (net (code "9") (name "/col8") (class "Default")
      (node (ref "S208") (pin "2") (pinfunction "2_2") (pintype "passive"))
      (node (ref "S222") (pin "2") (pinfunction "2_2") (pintype "passive"))
      (node (ref "S236") (pin "2") (pinfunction "2_2") (pintype "passive"))
      (node (ref "S250") (pin "2") (pinfunction "2_2") (pintype "passive"))
    )
    (net (code "10") (name "/col9") (class "Default")
      (node (ref "S209") (pin "2") (pinfunction "2_2") (pintype "passive"))
      (node (ref "S223") (pin "2") (pinfunction "2_2") (pintype "passive"))
      (node (ref "S237") (pin "2") (pinfunction "2_2") (pintype "passive"))
      (node (ref "S251") (pin "2") (pinfunction "2_2") (pintype "passive"))
      (node (ref "S263") (pin "1") (pinfunction "1_1") (pintype "passive"))
      (node (ref "S263_1") (pin "1") (pinfunction "1_1") (pintype "passive"))
      (node (ref "S263_2") (pin "1") (pinfunction "1_1") (pintype "passive"))
    )
    (net (code "11") (name "/col10") (class "Default")
      (node (ref "S210") (pin "2") (pinfunction "2_2") (pintype "passive"))
      (node (ref "S224") (pin "2") (pinfunction "2_2") (pintype "passive"))
      (node (ref "S238") (pin "2") (pinfunction "2_2") (pintype "passive"))
      (node (ref "S252") (pin "2") (pinfunction "2_2") (pintype "passive"))
      (node (ref "S264") (pin "2") (pinfunction "2_2") (pintype "passive"))
    )
    (net (code "12") (name "/col11") (class "Default")
      (node (ref "S211") (pin "2") (pinfunction "2_2") (pintype "passive"))
      (node (ref "S225") (pin "2") (pinfunction "2_2") (pintype "passive"))
      (node (ref "S239") (pin "2") (pinfunction "2_2") (pintype "passive"))
      (node (ref "S253") (pin "2") (pinfunction "2_2") (pintype "passive"))
      (node (ref "S265") (pin "1") (pinfunction "1_1") (pintype "passive"))
    )
    (net (code "13") (name "/col12") (class "Default")
      (node (ref "S212") (pin "2") (pinfunction "2_2") (pintype "passive"))
      (node (ref "S226") (pin "2") (pinfunction "2_2") (pintype "passive"))
      (node (ref "S240") (pin "2") (pinfunction "2_2") (pintype "passive"))
      (node (ref "S241") (pin "1") (pinfunction "1_1") (pintype "passive"))
      (node (ref "S254") (pin "2") (pinfunction "2_2") (pintype "passive"))
    )
    (net (code "14") (name "/col13") (class "Default")
      (node (ref "S213") (pin "2") (pinfunction "2_2") (pintype "passive"))
      (node (ref "S227") (pin "2") (pinfunction "2_2") (pintype "passive"))
      (node (ref "S228_2") (pin "2") (pinfunction "2_2") (pintype "passive"))
      (node (ref "S256") (pin "1") (pinfunction "1_1") (pintype "passive"))
      (node (ref "S266") (pin "2") (pinfunction "2_2") (pintype "passive"))
    )
    (net (code "15") (name "/col14") (class "Default")
      (node (ref "S214") (pin "2") (pinfunction "2_2") (pintype "passive"))
      (node (ref "S228") (pin "2") (pinfunction "2_2") (pintype "passive"))
      (node (ref "S242") (pin "2") (pinfunction "2_2") (pintype "passive"))
      (node (ref "S259") (pin "2") (pinfunction "2_2") (pintype "passive"))
      (node (ref "S269") (pin "2") (pinfunction "2_2") (pintype "passive"))
    )
    (net (code "16") (name "/row1") (class "Default")
      (node (ref "D201") (pin "2") (pinfunction "K_2") (pintype "passive"))
      (node (ref "D202") (pin "2") (pinfunction "K_2") (pintype "passive"))
      (node (ref "D203") (pin "2") (pinfunction "K_2") (pintype "passive"))
      (node (ref "D204") (pin "2") (pinfunction "K_2") (pintype "passive"))
      (node (ref "D205") (pin "2") (pinfunction "K_2") (pintype "passive"))
      (node (ref "D206") (pin "2") (pinfunction "K_2") (pintype "passive"))
      (node (ref "D207") (pin "2") (pinfunction "K_2") (pintype "passive"))
      (node (ref "D208") (pin "2") (pinfunction "K_2") (pintype "passive"))
      (node (ref "D209") (pin "2") (pinfunction "K_2") (pintype "passive"))
      (node (ref "D210") (pin "2") (pinfunction "K_2") (pintype "passive"))
      (node (ref "D211") (pin "2") (pinfunction "K_2") (pintype "passive"))
      (node (ref "D212") (pin "2") (pinfunction "K_2") (pintype "passive"))
      (node (ref "D213") (pin "2") (pinfunction "K_2") (pintype "passive"))
      (node (ref "D214") (pin "2") (pinfunction "K_2") (pintype "passive"))
    )
    (net (code "17") (name "/row2") (class "Default")
      (node (ref "D215") (pin "2") (pinfunction "K_2") (pintype "passive"))
      (node (ref "D216") (pin "2") (pinfunction "K_2") (pintype "passive"))
      (node (ref "D217") (pin "2") (pinfunction "K_2") (pintype "passive"))
      (node (ref "D218") (pin "2") (pinfunction "K_2") (pintype "passive"))
      (node (ref "D219") (pin "2") (pinfunction "K_2") (pintype "passive"))
      (node (ref "D220") (pin "2") (pinfunction "K_2") (pintype "passive"))
      (node (ref "D221") (pin "2") (pinfunction "K_2") (pintype "passive"))
      (node (ref "D222") (pin "2") (pinfunction "K_2") (pintype "passive"))
      (node (ref "D223") (pin "2") (pinfunction "K_2") (pintype "passive"))
      (node (ref "D224") (pin "2") (pinfunction "K_2") (pintype "passive"))
      (node (ref "D225") (pin "2") (pinfunction "K_2") (pintype "passive"))
      (node (ref "D226") (pin "2") (pinfunction "K_2") (pintype "passive"))
      (node (ref "D227") (pin "2") (pinfunction "K_2") (pintype "passive"))
      (node (ref "D228") (pin "2") (pinfunction "K_2") (pintype "passive"))
    )
    (net (code "18") (name "/row3") (class "Default")
      (node (ref "D228_2") (pin "2") (pinfunction "K_2") (pintype "passive"))
      (node (ref "D229") (pin "2") (pinfunction "K_2") (pintype "passive"))
      (node (ref "D230") (pin "2") (pinfunction "K_2") (pintype "passive"))
      (node (ref "D231") (pin "2") (pinfunction "K_2") (pintype "passive"))
      (node (ref "D232") (pin "2") (pinfunction "K_2") (pintype "passive"))
      (node (ref "D233") (pin "2") (pinfunction "K_2") (pintype "passive"))
      (node (ref "D234") (pin "2") (pinfunction "K_2") (pintype "passive"))
      (node (ref "D235") (pin "2") (pinfunction "K_2") (pintype "passive"))
      (node (ref "D236") (pin "2") (pinfunction "K_2") (pintype "passive"))
      (node (ref "D237") (pin "2") (pinfunction "K_2") (pintype "passive"))
      (node (ref "D238") (pin "2") (pinfunction "K_2") (pintype "passive"))
      (node (ref "D239") (pin "2") (pinfunction "K_2") (pintype "passive"))
      (node (ref "D240") (pin "2") (pinfunction "K_2") (pintype "passive"))
      (node (ref "D259") (pin "2") (pinfunction "K_2") (pintype "passive"))
    )
    (net (code "19") (name "/row4") (class "Default")
      (node (ref "D242") (pin "2") (pinfunction "K_2") (pintype "passive"))
      (node (ref "D243") (pin "2") (pinfunction "K_2") (pintype "passive"))
      (node (ref "D244") (pin "2") (pinfunction "K_2") (pintype "passive"))
      (node (ref "D245") (pin "2") (pinfunction "K_2") (pintype "passive"))
      (node (ref "D246") (pin "2") (pinfunction "K_2") (pintype "passive"))
      (node (ref "D247") (pin "2") (pinfunction "K_2") (pintype "passive"))
      (node (ref "D248") (pin "2") (pinfunction "K_2") (pintype "passive"))
      (node (ref "D249") (pin "2") (pinfunction "K_2") (pintype "passive"))
      (node (ref "D250") (pin "2") (pinfunction "K_2") (pintype "passive"))
      (node (ref "D251") (pin "2") (pinfunction "K_2") (pintype "passive"))
      (node (ref "D252") (pin "2") (pinfunction "K_2") (pintype "passive"))
      (node (ref "D253") (pin "2") (pinfunction "K_2") (pintype "passive"))
      (node (ref "D254") (pin "2") (pinfunction "K_2") (pintype "passive"))
      (node (ref "D255") (pin "2") (pinfunction "K_2") (pintype "passive"))
    )
    (net (code "20") (name "/row5") (class "Default")
      (node (ref "D241") (pin "2") (pinfunction "K_2") (pintype "passive"))
      (node (ref "D256") (pin "2") (pinfunction "K_2") (pintype "passive"))
      (node (ref "D257") (pin "2") (pinfunction "K_2") (pintype "passive"))
      (node (ref "D258") (pin "2") (pinfunction "K_2") (pintype "passive"))
      (node (ref "D260") (pin "2") (pinfunction "K_2") (pintype "passive"))
      (node (ref "D261") (pin "2") (pinfunction "K_2") (pintype "passive"))
      (node (ref "D262") (pin "2") (pinfunction "K_2") (pintype "passive"))
      (node (ref "D263") (pin "2") (pinfunction "K_2") (pintype "passive"))
      (node (ref "D264") (pin "2") (pinfunction "K_2") (pintype "passive"))
      (node (ref "D265") (pin "2") (pinfunction "K_2") (pintype "passive"))
      (node (ref "D266") (pin "2") (pinfunction "K_2") (pintype "passive"))
    )
    (net (code "21") (name "Net-(D201-A)") (class "Default")
      (node (ref "D201") (pin "1") (pinfunction "A_1") (pintype "passive"))
      (node (ref "S201") (pin "1") (pinfunction "1_1") (pintype "passive"))
    )
    (net (code "22") (name "Net-(D202-A)") (class "Default")
      (node (ref "D202") (pin "1") (pinfunction "A_1") (pintype "passive"))
      (node (ref "S202") (pin "1") (pinfunction "1_1") (pintype "passive"))
    )
    (net (code "23") (name "Net-(D203-A)") (class "Default")
      (node (ref "D203") (pin "1") (pinfunction "A_1") (pintype "passive"))
      (node (ref "S203") (pin "1") (pinfunction "1_1") (pintype "passive"))
    )
    (net (code "24") (name "Net-(D204-A)") (class "Default")
      (node (ref "D204") (pin "1") (pinfunction "A_1") (pintype "passive"))
      (node (ref "S204") (pin "1") (pinfunction "1_1") (pintype "passive"))
    )
    (net (code "25") (name "Net-(D205-A)") (class "Default")
      (node (ref "D205") (pin "1") (pinfunction "A_1") (pintype "passive"))
      (node (ref "S205") (pin "1") (pinfunction "1_1") (pintype "passive"))
    )
    (net (code "26") (name "Net-(D206-A)") (class "Default")
      (node (ref "D206") (pin "1") (pinfunction "A_1") (pintype "passive"))
      (node (ref "S206") (pin "1") (pinfunction "1_1") (pintype "passive"))
    )
    (net (code "27") (name "Net-(D207-A)") (class "Default")
      (node (ref "D207") (pin "1") (pinfunction "A_1") (pintype "passive"))
      (node (ref "S207") (pin "1") (pinfunction "1_1") (pintype "passive"))
    )
    (net (code "28") (name "Net-(D208-A)") (class "Default")
      (node (ref "D208") (pin "1") (pinfunction "A_1") (pintype "passive"))
      (node (ref "S208") (pin "1") (pinfunction "1_1") (pintype "passive"))
    )
    (net (code "29") (name "Net-(D209-A)") (class "Default")
      (node (ref "D209") (pin "1") (pinfunction "A_1") (pintype "passive"))
      (node (ref "S209") (pin "1") (pinfunction "1_1") (pintype "passive"))
    )
    (net (code "30") (name "Net-(D210-A)") (class "Default")
      (node (ref "D210") (pin "1") (pinfunction "A_1") (pintype "passive"))
      (node (ref "S210") (pin "1") (pinfunction "1_1") (pintype "passive"))
    )
    (net (code "31") (name "Net-(D211-A)") (class "Default")
      (node (ref "D211") (pin "1") (pinfunction "A_1") (pintype "passive"))
      (node (ref "S211") (pin "1") (pinfunction "1_1") (pintype "passive"))
    )
    (net (code "32") (name "Net-(D212-A)") (class "Default")
      (node (ref "D212") (pin "1") (pinfunction "A_1") (pintype "passive"))
      (node (ref "S212") (pin "1") (pinfunction "1_1") (pintype "passive"))
    )
    (net (code "33") (name "Net-(D213-A)") (class "Default")
      (node (ref "D213") (pin "1") (pinfunction "A_1") (pintype "passive"))
      (node (ref "S213") (pin "1") (pinfunction "1_1") (pintype "passive"))
    )
    (net (code "34") (name "Net-(D214-A)") (class "Default")
      (node (ref "D214") (pin "1") (pinfunction "A_1") (pintype "passive"))
      (node (ref "S214") (pin "1") (pinfunction "1_1") (pintype "passive"))
    )
    (net (code "35") (name "Net-(D215-A)") (class "Default")
      (node (ref "D215") (pin "1") (pinfunction "A_1") (pintype "passive"))
      (node (ref "S215") (pin "1") (pinfunction "1_1") (pintype "passive"))
    )
    (net (code "36") (name "Net-(D216-A)") (class "Default")
      (node (ref "D216") (pin "1") (pinfunction "A_1") (pintype "passive"))
      (node (ref "S216") (pin "1") (pinfunction "1_1") (pintype "passive"))
    )
    (net (code "37") (name "Net-(D217-A)") (class "Default")
      (node (ref "D217") (pin "1") (pinfunction "A_1") (pintype "passive"))
      (node (ref "S217") (pin "1") (pinfunction "1_1") (pintype "passive"))
    )
    (net (code "38") (name "Net-(D218-A)") (class "Default")
      (node (ref "D218") (pin "1") (pinfunction "A_1") (pintype "passive"))
      (node (ref "S218") (pin "1") (pinfunction "1_1") (pintype "passive"))
    )
    (net (code "39") (name "Net-(D219-A)") (class "Default")
      (node (ref "D219") (pin "1") (pinfunction "A_1") (pintype "passive"))
      (node (ref "S219") (pin "1") (pinfunction "1_1") (pintype "passive"))
    )
    (net (code "40") (name "Net-(D220-A)") (class "Default")
      (node (ref "D220") (pin "1") (pinfunction "A_1") (pintype "passive"))
      (node (ref "S220") (pin "1") (pinfunction "1_1") (pintype "passive"))
    )
    (net (code "41") (name "Net-(D221-A)") (class "Default")
      (node (ref "D221") (pin "1") (pinfunction "A_1") (pintype "passive"))
      (node (ref "S221") (pin "1") (pinfunction "1_1") (pintype "passive"))
    )
    (net (code "42") (name "Net-(D222-A)") (class "Default")
      (node (ref "D222") (pin "1") (pinfunction "A_1") (pintype "passive"))
      (node (ref "S222") (pin "1") (pinfunction "1_1") (pintype "passive"))
    )
    (net (code "43") (name "Net-(D223-A)") (class "Default")
      (node (ref "D223") (pin "1") (pinfunction "A_1") (pintype "passive"))
      (node (ref "S223") (pin "1") (pinfunction "1_1") (pintype "passive"))
    )
    (net (code "44") (name "Net-(D224-A)") (class "Default")
      (node (ref "D224") (pin "1") (pinfunction "A_1") (pintype "passive"))
      (node (ref "S224") (pin "1") (pinfunction "1_1") (pintype "passive"))
    )
    (net (code "45") (name "Net-(D225-A)") (class "Default")
      (node (ref "D225") (pin "1") (pinfunction "A_1") (pintype "passive"))
      (node (ref "S225") (pin "1") (pinfunction "1_1") (pintype "passive"))
    )
    (net (code "46") (name "Net-(D226-A)") (class "Default")
      (node (ref "D226") (pin "1") (pinfunction "A_1") (pintype "passive"))
      (node (ref "S226") (pin "1") (pinfunction "1_1") (pintype "passive"))
    )
    (net (code "47") (name "Net-(D227-A)") (class "Default")
      (node (ref "D227") (pin "1") (pinfunction "A_1") (pintype "passive"))
      (node (ref "S227") (pin "1") (pinfunction "1_1") (pintype "passive"))
    )
    (net (code "48") (name "Net-(D228-A)") (class "Default")
      (node (ref "D228") (pin "1") (pinfunction "A_1") (pintype "passive"))
      (node (ref "S228") (pin "1") (pinfunction "1_1") (pintype "passive"))
    )
    (net (code "49") (name "Net-(D228_2-A)") (class "Default")
      (node (ref "D228_2") (pin "1") (pinfunction "A_1") (pintype "passive"))
      (node (ref "S228_2") (pin "1") (pinfunction "1_1") (pintype "passive"))
    )
    (net (code "50") (name "Net-(D229-A)") (class "Default")
      (node (ref "D229") (pin "1") (pinfunction "A_1") (pintype "passive"))
      (node (ref "S229") (pin "1") (pinfunction "1_1") (pintype "passive"))
    )
    (net (code "51") (name "Net-(D230-A)") (class "Default")
      (node (ref "D230") (pin "1") (pinfunction "A_1") (pintype "passive"))
      (node (ref "S230") (pin "1") (pinfunction "1_1") (pintype "passive"))
    )
    (net (code "52") (name "Net-(D231-A)") (class "Default")
      (node (ref "D231") (pin "1") (pinfunction "A_1") (pintype "passive"))
      (node (ref "S231") (pin "1") (pinfunction "1_1") (pintype "passive"))
    )
    (net (code "53") (name "Net-(D232-A)") (class "Default")
      (node (ref "D232") (pin "1") (pinfunction "A_1") (pintype "passive"))
      (node (ref "S232") (pin "1") (pinfunction "1_1") (pintype "passive"))
    )
    (net (code "54") (name "Net-(D233-A)") (class "Default")
      (node (ref "D233") (pin "1") (pinfunction "A_1") (pintype "passive"))
      (node (ref "S233") (pin "1") (pinfunction "1_1") (pintype "passive"))
    )
    (net (code "55") (name "Net-(D234-A)") (class "Default")
      (node (ref "D234") (pin "1") (pinfunction "A_1") (pintype "passive"))
      (node (ref "S234") (pin "1") (pinfunction "1_1") (pintype "passive"))
    )
    (net (code "56") (name "Net-(D235-A)") (class "Default")
      (node (ref "D235") (pin "1") (pinfunction "A_1") (pintype "passive"))
      (node (ref "S235") (pin "1") (pinfunction "1_1") (pintype "passive"))
    )
    (net (code "57") (name "Net-(D236-A)") (class "Default")
      (node (ref "D236") (pin "1") (pinfunction "A_1") (pintype "passive"))
      (node (ref "S236") (pin "1") (pinfunction "1_1") (pintype "passive"))
    )
    (net (code "58") (name "Net-(D237-A)") (class "Default")
      (node (ref "D237") (pin "1") (pinfunction "A_1") (pintype "passive"))
      (node (ref "S237") (pin "1") (pinfunction "1_1") (pintype "passive"))
    )
    (net (code "59") (name "Net-(D238-A)") (class "Default")
      (node (ref "D238") (pin "1") (pinfunction "A_1") (pintype "passive"))
      (node (ref "S238") (pin "1") (pinfunction "1_1") (pintype "passive"))
    )
    (net (code "60") (name "Net-(D239-A)") (class "Default")
      (node (ref "D239") (pin "1") (pinfunction "A_1") (pintype "passive"))
      (node (ref "S239") (pin "1") (pinfunction "1_1") (pintype "passive"))
    )
    (net (code "61") (name "Net-(D240-A)") (class "Default")
      (node (ref "D240") (pin "1") (pinfunction "A_1") (pintype "passive"))
      (node (ref "S240") (pin "1") (pinfunction "1_1") (pintype "passive"))
    )
    (net (code "62") (name "Net-(D241-A)") (class "Default")
      (node (ref "D241") (pin "1") (pinfunction "A_1") (pintype "passive"))
      (node (ref "S241") (pin "2") (pinfunction "2_2") (pintype "passive"))
    )
    (net (code "63") (name "Net-(D242-A)") (class "Default")
      (node (ref "D242") (pin "1") (pinfunction "A_1") (pintype "passive"))
      (node (ref "S242") (pin "1") (pinfunction "1_1") (pintype "passive"))
    )
    (net (code "64") (name "Net-(D243-A)") (class "Default")
      (node (ref "D243") (pin "1") (pinfunction "A_1") (pintype "passive"))
      (node (ref "S243") (pin "1") (pinfunction "1_1") (pintype "passive"))
    )
    (net (code "65") (name "Net-(D244-A)") (class "Default")
      (node (ref "D244") (pin "1") (pinfunction "A_1") (pintype "passive"))
      (node (ref "S244") (pin "2") (pinfunction "2_2") (pintype "passive"))
    )
    (net (code "66") (name "Net-(D245-A)") (class "Default")
      (node (ref "D245") (pin "1") (pinfunction "A_1") (pintype "passive"))
      (node (ref "S245") (pin "1") (pinfunction "1_1") (pintype "passive"))
    )
    (net (code "67") (name "Net-(D246-A)") (class "Default")
      (node (ref "D246") (pin "1") (pinfunction "A_1") (pintype "passive"))
      (node (ref "S246") (pin "1") (pinfunction "1_1") (pintype "passive"))
    )
    (net (code "68") (name "Net-(D247-A)") (class "Default")
      (node (ref "D247") (pin "1") (pinfunction "A_1") (pintype "passive"))
      (node (ref "S247") (pin "1") (pinfunction "1_1") (pintype "passive"))
    )
    (net (code "69") (name "Net-(D248-A)") (class "Default")
      (node (ref "D248") (pin "1") (pinfunction "A_1") (pintype "passive"))
      (node (ref "S248") (pin "1") (pinfunction "1_1") (pintype "passive"))
    )
    (net (code "70") (name "Net-(D249-A)") (class "Default")
      (node (ref "D249") (pin "1") (pinfunction "A_1") (pintype "passive"))
      (node (ref "S249") (pin "1") (pinfunction "1_1") (pintype "passive"))
    )
    (net (code "71") (name "Net-(D250-A)") (class "Default")
      (node (ref "D250") (pin "1") (pinfunction "A_1") (pintype "passive"))
      (node (ref "S250") (pin "1") (pinfunction "1_1") (pintype "passive"))
    )
    (net (code "72") (name "Net-(D251-A)") (class "Default")
      (node (ref "D251") (pin "1") (pinfunction "A_1") (pintype "passive"))
      (node (ref "S251") (pin "1") (pinfunction "1_1") (pintype "passive"))
    )
    (net (code "73") (name "Net-(D252-A)") (class "Default")
      (node (ref "D252") (pin "1") (pinfunction "A_1") (pintype "passive"))
      (node (ref "S252") (pin "1") (pinfunction "1_1") (pintype "passive"))
    )
    (net (code "74") (name "Net-(D253-A)") (class "Default")
      (node (ref "D253") (pin "1") (pinfunction "A_1") (pintype "passive"))
      (node (ref "S253") (pin "1") (pinfunction "1_1") (pintype "passive"))
    )
    (net (code "75") (name "Net-(D254-A)") (class "Default")
      (node (ref "D254") (pin "1") (pinfunction "A_1") (pintype "passive"))
      (node (ref "S254") (pin "1") (pinfunction "1_1") (pintype "passive"))
    )
    (net (code "76") (name "Net-(D255-A)") (class "Default")
      (node (ref "D255") (pin "1") (pinfunction "A_1") (pintype "passive"))
      (node (ref "S256") (pin "2") (pinfunction "2_2") (pintype "passive"))
    )
    (net (code "77") (name "Net-(D256-A)") (class "Default")
      (node (ref "D256") (pin "1") (pinfunction "A_1") (pintype "passive"))
      (node (ref "S269") (pin "1") (pinfunction "1_1") (pintype "passive"))
    )
    (net (code "78") (name "Net-(D257-A)") (class "Default")
      (node (ref "D257") (pin "1") (pinfunction "A_1") (pintype "passive"))
      (node (ref "S257") (pin "2") (pinfunction "2_2") (pintype "passive"))
    )
    (net (code "79") (name "Net-(D258-A)") (class "Default")
      (node (ref "D258") (pin "1") (pinfunction "A_1") (pintype "passive"))
      (node (ref "S258") (pin "1") (pinfunction "1_1") (pintype "passive"))
    )
    (net (code "80") (name "Net-(D260-A)") (class "Default")
      (node (ref "D260") (pin "1") (pinfunction "A_1") (pintype "passive"))
      (node (ref "S260") (pin "1") (pinfunction "1_1") (pintype "passive"))
      (node (ref "S260_1") (pin "1") (pinfunction "1_1") (pintype "passive"))
    )
    (net (code "81") (name "Net-(D261-A)") (class "Default")
      (node (ref "D261") (pin "1") (pinfunction "A_1") (pintype "passive"))
      (node (ref "S261") (pin "1") (pinfunction "1_1") (pintype "passive"))
      (node (ref "S261_1") (pin "1") (pinfunction "1_1") (pintype "passive"))
      (node (ref "S261_2") (pin "2") (pinfunction "2_2") (pintype "passive"))
      (node (ref "S261_3") (pin "1") (pinfunction "1_1") (pintype "passive"))
    )
    (net (code "82") (name "Net-(D262-A)") (class "Default")
      (node (ref "D262") (pin "1") (pinfunction "A_1") (pintype "passive"))
      (node (ref "S262") (pin "2") (pinfunction "2_2") (pintype "passive"))
    )
    (net (code "83") (name "Net-(D263-A)") (class "Default")
      (node (ref "D263") (pin "1") (pinfunction "A_1") (pintype "passive"))
      (node (ref "S263") (pin "2") (pinfunction "2_2") (pintype "passive"))
      (node (ref "S263_1") (pin "2") (pinfunction "2_2") (pintype "passive"))
      (node (ref "S263_2") (pin "2") (pinfunction "2_2") (pintype "passive"))
    )
    (net (code "84") (name "Net-(D264-A)") (class "Default")
      (node (ref "D264") (pin "1") (pinfunction "A_1") (pintype "passive"))
      (node (ref "S264") (pin "1") (pinfunction "1_1") (pintype "passive"))
    )
    (net (code "85") (name "Net-(D265-A)") (class "Default")
      (node (ref "D265") (pin "1") (pinfunction "A_1") (pintype "passive"))
      (node (ref "S265") (pin "2") (pinfunction "2_2") (pintype "passive"))
    )
    (net (code "86") (name "Net-(D266-A)") (class "Default")
      (node (ref "D266") (pin "1") (pinfunction "A_1") (pintype "passive"))
      (node (ref "S266") (pin "1") (pinfunction "1_1") (pintype "passive"))
    )
    (net (code "87") (name "unconnected-(STAB1-Pad1)") (class "Default")
      (node (ref "STAB1") (pin "1") (pinfunction "1_1") (pintype "passive"))
    )
  )
)
